# hacker.net
KiCad netlist of a schematic drawn in EAGLE
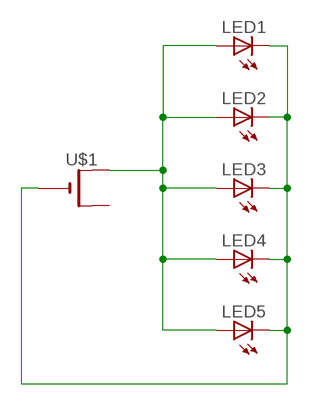
[diagram p0: schematic, sheet 1]

(export (version "E")
  (design (tool "Eeschema 10.0.6"))
  (components
    (comp (ref "LED1")
      (value "LED5MM")
      (footprint "eagle-import:LED5MM")
      (libsource (lib "eagle-import") (part "LED5MM"))
    )
    (comp (ref "LED2")
      (value "LED5MM")
      (footprint "eagle-import:LED5MM")
      (libsource (lib "eagle-import") (part "LED5MM"))
    )
    (comp (ref "LED3")
      (value "LED5MM")
      (footprint "eagle-import:LED5MM")
      (libsource (lib "eagle-import") (part "LED5MM"))
    )
    (comp (ref "LED4")
      (value "LED5MM")
      (footprint "eagle-import:LED5MM")
      (libsource (lib "eagle-import") (part "LED5MM"))
    )
    (comp (ref "LED5")
      (value "LED5MM")
      (footprint "eagle-import:LED5MM")
      (libsource (lib "eagle-import") (part "LED5MM"))
    )
    (comp (ref "U$1")
      (value "CR1220THM")
      (footprint "eagle-import:CR1220-THM")
      (libsource (lib "eagle-import") (part "CR1220THM"))
    )
  )
  (nets
    (net (code "1") (name "Net-(LED1-C)") (class "Default")
      (node (ref "LED1") (pin "K") (pinfunction "C_K") (pintype "passive"))
      (node (ref "LED2") (pin "K") (pinfunction "C_K") (pintype "passive"))
      (node (ref "LED3") (pin "K") (pinfunction "C_K") (pintype "passive"))
      (node (ref "LED4") (pin "K") (pinfunction "C_K") (pintype "passive"))
      (node (ref "LED5") (pin "K") (pinfunction "C_K") (pintype "passive"))
      (node (ref "U$1") (pin "-") (pinfunction "-_-") (pintype "passive"))
    )
    (net (code "2") (name "Net-(U$1-+)") (class "Default")
      (node (ref "LED1") (pin "A") (pinfunction "A_A") (pintype "passive"))
      (node (ref "LED2") (pin "A") (pinfunction "A_A") (pintype "passive"))
      (node (ref "LED3") (pin "A") (pinfunction "A_A") (pintype "passive"))
      (node (ref "LED4") (pin "A") (pinfunction "A_A") (pintype "passive"))
      (node (ref "LED5") (pin "A") (pinfunction "A_A") (pintype "passive"))
      (node (ref "U$1") (pin "+1") (pinfunction "+_+1") (pintype "passive"))
    )
    (net (code "3") (name "unconnected-(U$1-+1-Pad+2)") (class "Default")
      (node (ref "U$1") (pin "+2") (pinfunction "+1_+2") (pintype "passive"))
    )
  )
)
